# PSPS_AVNC_SRD_central-2020-09-28.net
KiCad netlist of a schematic drawn in EAGLE
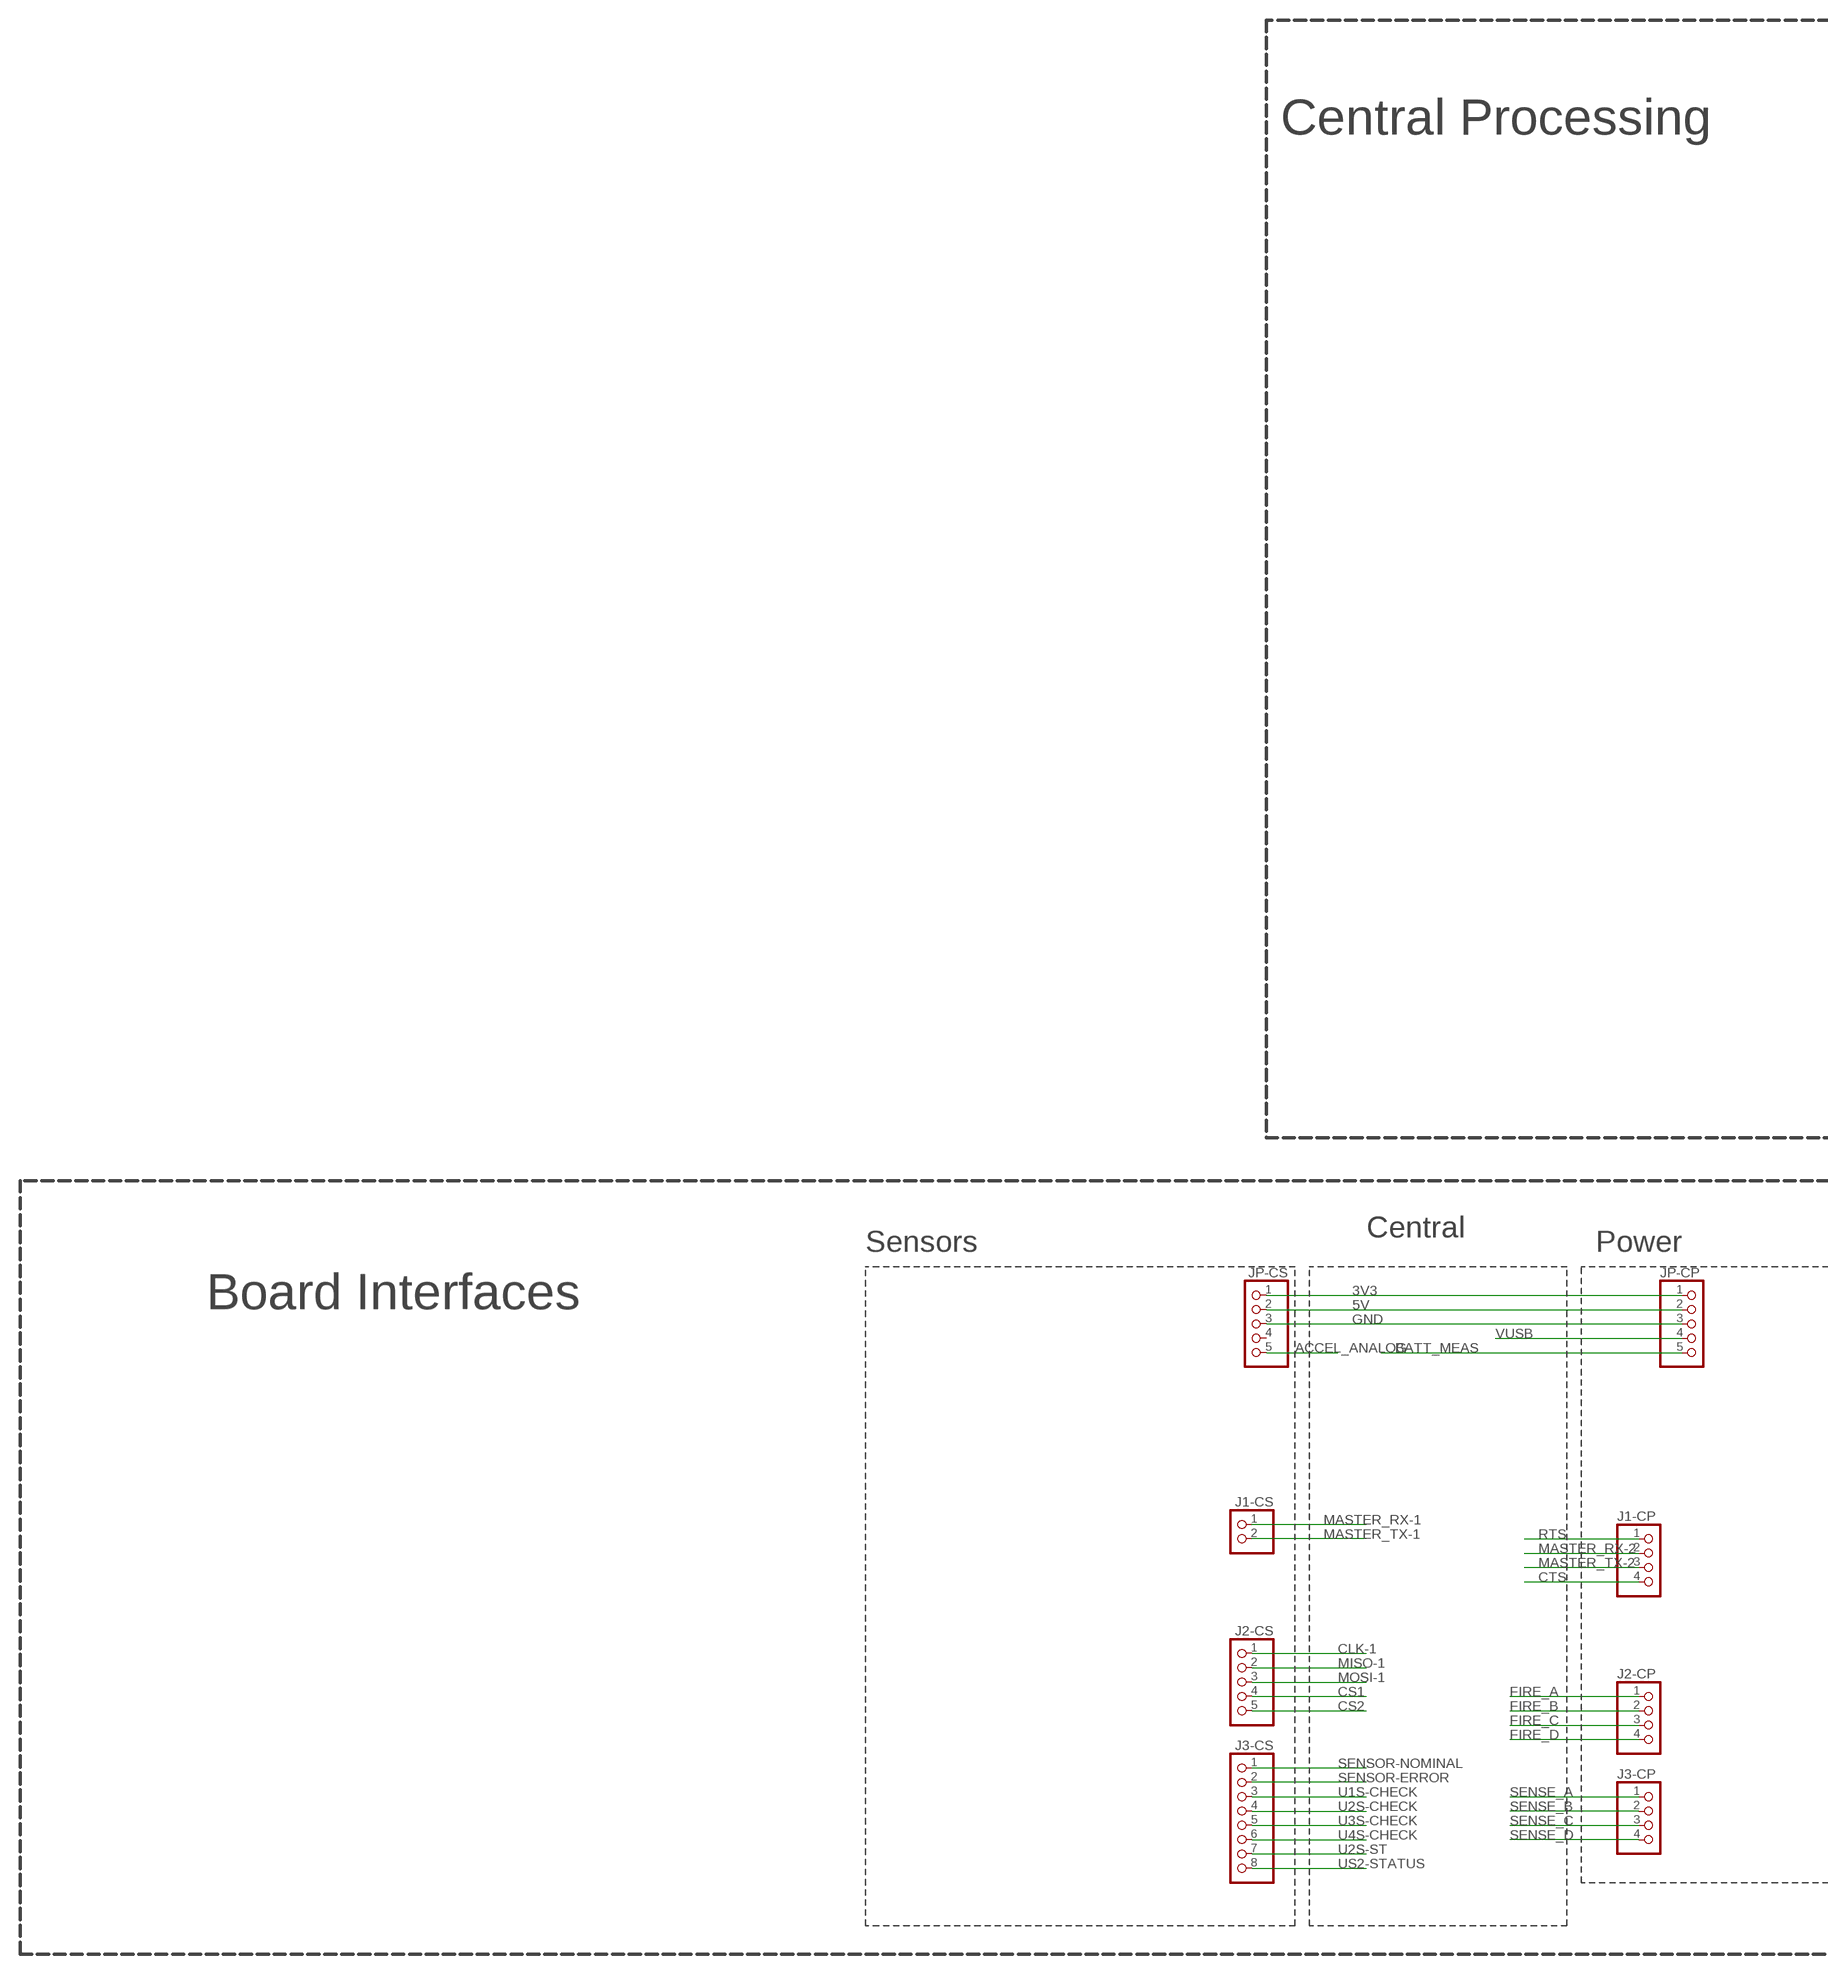
[diagram p0: schematic, sheet 1, part 1 of 2]
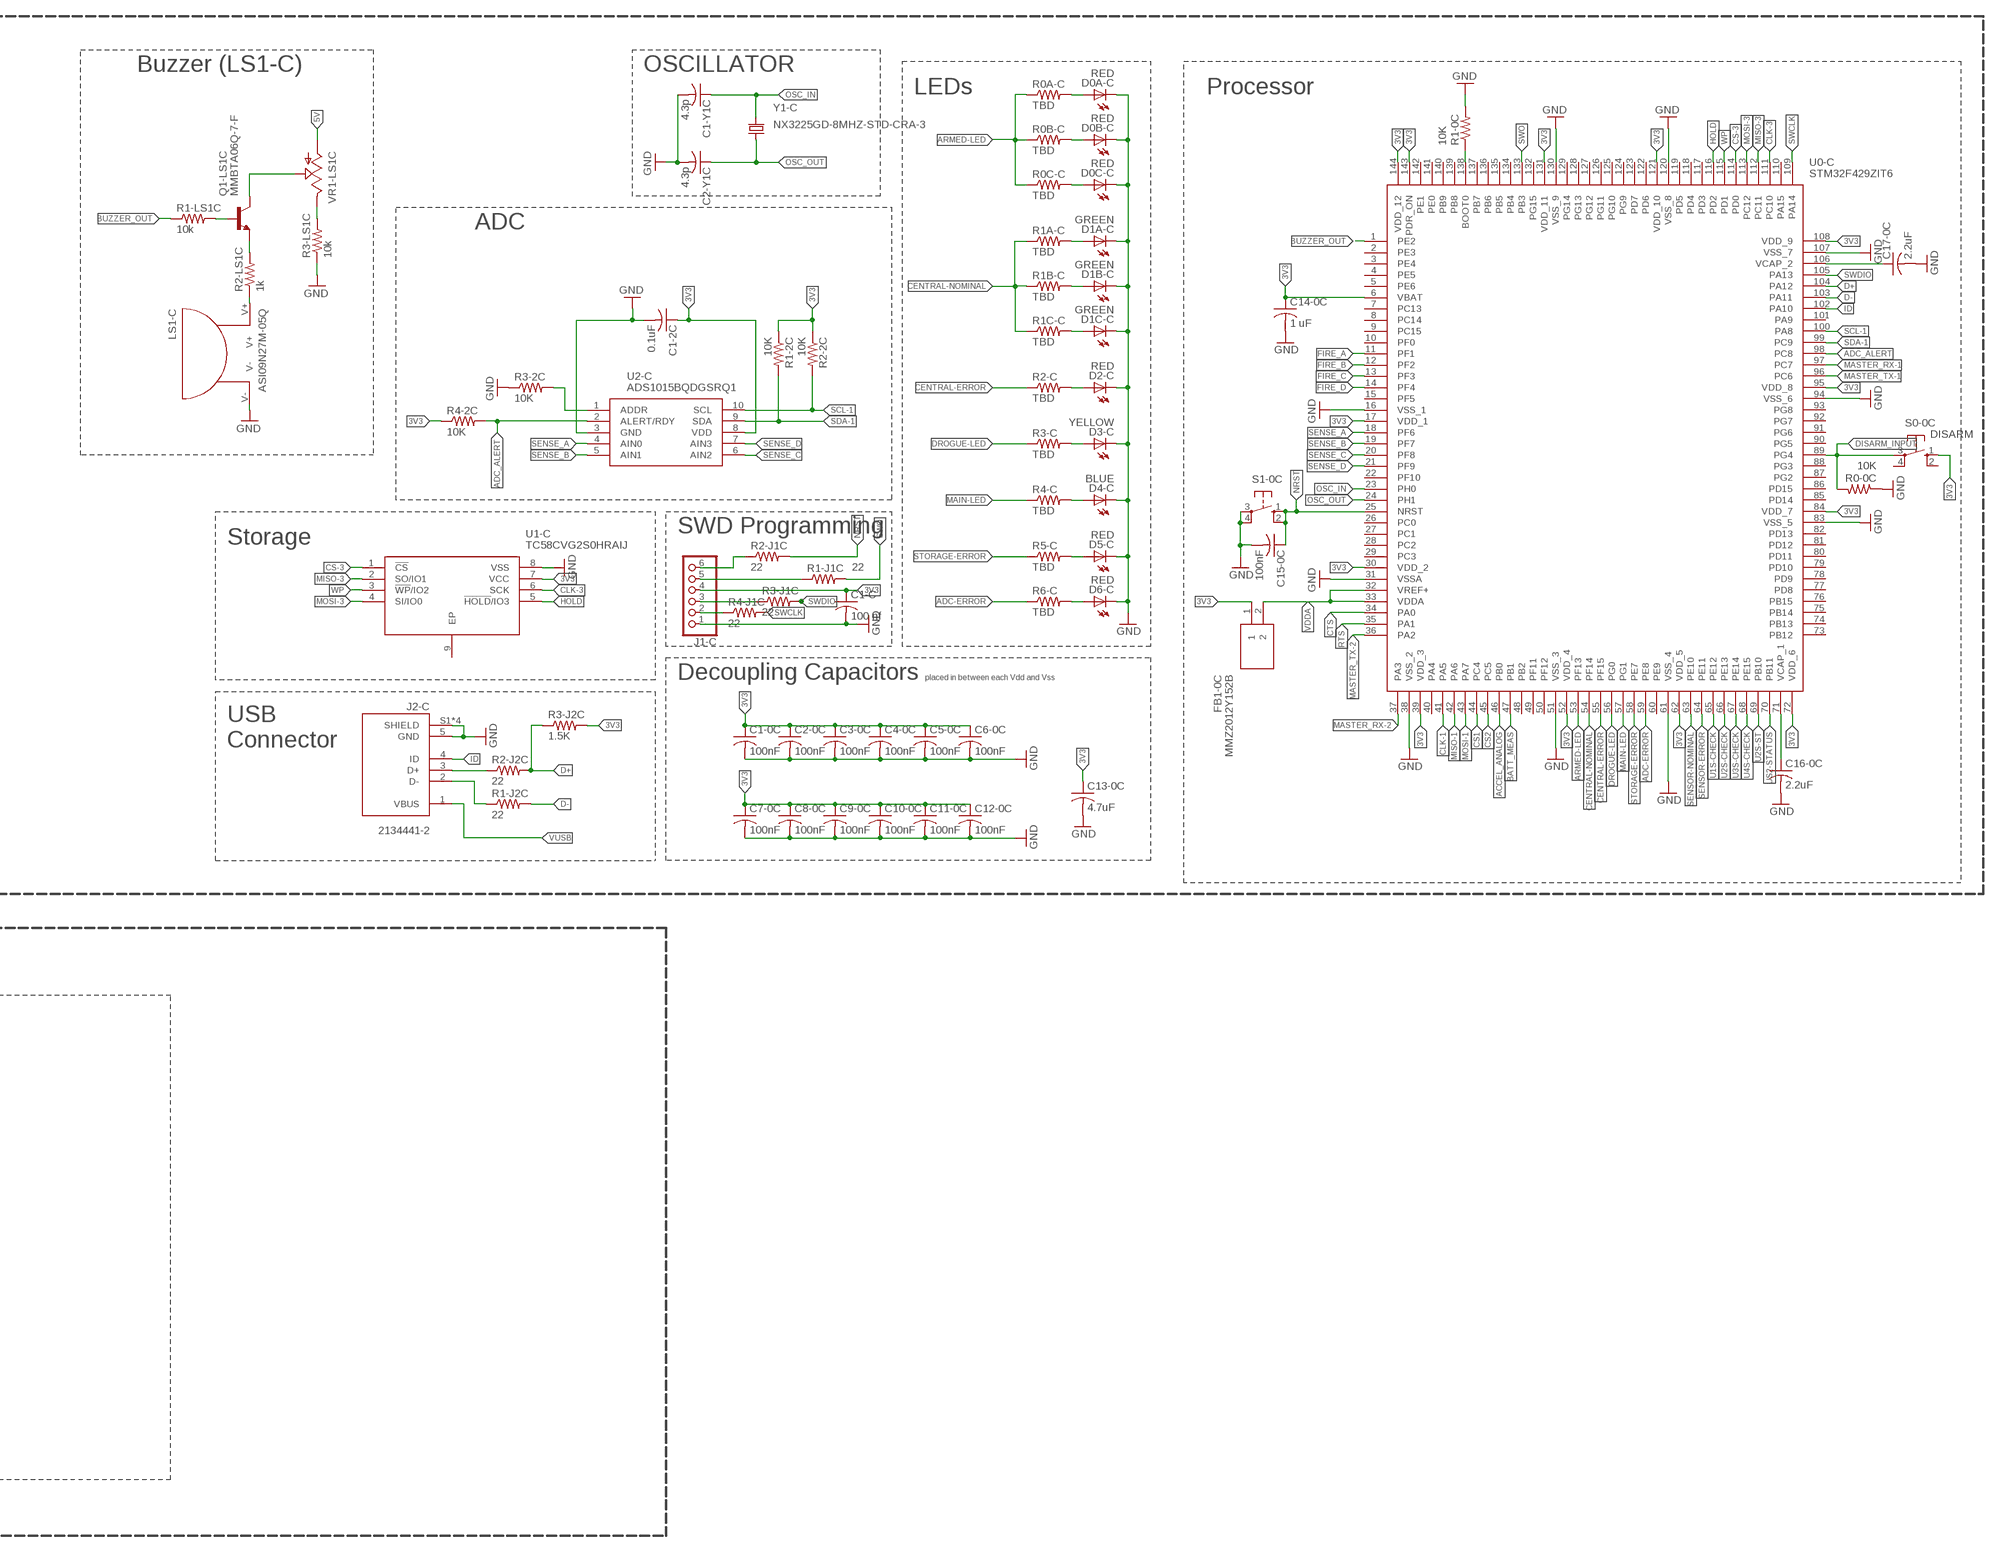
[diagram p1: schematic, sheet 1, part 2 of 2]

(export (version "E")
  (design (tool "Eeschema 10.0.6"))
  (components
    (comp (ref "C1-0C")
      (value "100nF")
      (footprint "eagle-import:C0805")
      (libsource (lib "eagle-import") (part "C-USC0805"))
    )
    (comp (ref "C1-2C")
      (value "0.1uF")
      (footprint "eagle-import:C0805")
      (libsource (lib "eagle-import") (part "C-USC0805"))
    )
    (comp (ref "C1-C")
      (value "100 nf")
      (footprint "eagle-import:C0805")
      (libsource (lib "eagle-import") (part "C-USC0805"))
    )
    (comp (ref "C1-Y1C")
      (value "4.3p")
      (footprint "eagle-import:C0805")
      (libsource (lib "eagle-import") (part "C-USC0805"))
    )
    (comp (ref "C2-0C")
      (value "100nF")
      (footprint "eagle-import:C0805")
      (libsource (lib "eagle-import") (part "C-USC0805"))
    )
    (comp (ref "C2-Y1C")
      (value "4.3p")
      (footprint "eagle-import:C0805")
      (libsource (lib "eagle-import") (part "C-USC0805"))
    )
    (comp (ref "C3-0C")
      (value "100nF")
      (footprint "eagle-import:C0805")
      (libsource (lib "eagle-import") (part "C-USC0805"))
    )
    (comp (ref "C4-0C")
      (value "100nF")
      (footprint "eagle-import:C0805")
      (libsource (lib "eagle-import") (part "C-USC0805"))
    )
    (comp (ref "C5-0C")
      (value "100nF")
      (footprint "eagle-import:C0805")
      (libsource (lib "eagle-import") (part "C-USC0805"))
    )
    (comp (ref "C6-0C")
      (value "100nF")
      (footprint "eagle-import:C0805")
      (libsource (lib "eagle-import") (part "C-USC0805"))
    )
    (comp (ref "C7-0C")
      (value "100nF")
      (footprint "eagle-import:C0805")
      (libsource (lib "eagle-import") (part "C-USC0805"))
    )
    (comp (ref "C8-0C")
      (value "100nF")
      (footprint "eagle-import:C0805")
      (libsource (lib "eagle-import") (part "C-USC0805"))
    )
    (comp (ref "C9-0C")
      (value "100nF")
      (footprint "eagle-import:C0805")
      (libsource (lib "eagle-import") (part "C-USC0805"))
    )
    (comp (ref "C10-0C")
      (value "100nF")
      (footprint "eagle-import:C0805")
      (libsource (lib "eagle-import") (part "C-USC0805"))
    )
    (comp (ref "C11-0C")
      (value "100nF")
      (footprint "eagle-import:C0805")
      (libsource (lib "eagle-import") (part "C-USC0805"))
    )
    (comp (ref "C12-0C")
      (value "100nF")
      (footprint "eagle-import:C0805")
      (libsource (lib "eagle-import") (part "C-USC0805"))
    )
    (comp (ref "C13-0C")
      (value "4.7uF")
      (footprint "eagle-import:C0805")
      (libsource (lib "eagle-import") (part "C-USC0805"))
    )
    (comp (ref "C14-0C")
      (value "1 uF")
      (footprint "eagle-import:C0805")
      (libsource (lib "eagle-import") (part "C-USC0805"))
    )
    (comp (ref "C15-0C")
      (value "100nF")
      (footprint "eagle-import:C0805")
      (libsource (lib "eagle-import") (part "C-USC0805"))
    )
    (comp (ref "C16-0C")
      (value "2.2uF")
      (footprint "eagle-import:C0805")
      (libsource (lib "eagle-import") (part "C-USC0805"))
    )
    (comp (ref "C17-0C")
      (value "2.2uF")
      (footprint "eagle-import:C0805")
      (libsource (lib "eagle-import") (part "C-USC0805"))
    )
    (comp (ref "D0A-C")
      (value "RED")
      (footprint "eagle-import:CHIPLED_0805")
      (libsource (lib "eagle-import") (part "LEDCHIPLED_0805"))
    )
    (comp (ref "D0B-C")
      (value "RED")
      (footprint "eagle-import:CHIPLED_0805")
      (libsource (lib "eagle-import") (part "LEDCHIPLED_0805"))
    )
    (comp (ref "D0C-C")
      (value "RED")
      (footprint "eagle-import:CHIPLED_0805")
      (libsource (lib "eagle-import") (part "LEDCHIPLED_0805"))
    )
    (comp (ref "D1A-C")
      (value "GREEN")
      (footprint "eagle-import:CHIPLED_0805")
      (libsource (lib "eagle-import") (part "LEDCHIPLED_0805"))
    )
    (comp (ref "D1B-C")
      (value "GREEN")
      (footprint "eagle-import:CHIPLED_0805")
      (libsource (lib "eagle-import") (part "LEDCHIPLED_0805"))
    )
    (comp (ref "D1C-C")
      (value "GREEN")
      (footprint "eagle-import:CHIPLED_0805")
      (libsource (lib "eagle-import") (part "LEDCHIPLED_0805"))
    )
    (comp (ref "D2-C")
      (value "RED")
      (footprint "eagle-import:CHIPLED_0805")
      (libsource (lib "eagle-import") (part "LEDCHIPLED_0805"))
    )
    (comp (ref "D3-C")
      (value "YELLOW")
      (footprint "eagle-import:CHIPLED_0805")
      (libsource (lib "eagle-import") (part "LEDCHIPLED_0805"))
    )
    (comp (ref "D4-C")
      (value "BLUE")
      (footprint "eagle-import:CHIPLED_0805")
      (libsource (lib "eagle-import") (part "LEDCHIPLED_0805"))
    )
    (comp (ref "D5-C")
      (value "RED")
      (footprint "eagle-import:CHIPLED_0805")
      (libsource (lib "eagle-import") (part "LEDCHIPLED_0805"))
    )
    (comp (ref "D6-C")
      (value "RED")
      (footprint "eagle-import:CHIPLED_0805")
      (libsource (lib "eagle-import") (part "LEDCHIPLED_0805"))
    )
    (comp (ref "FB1-0C")
      (value "MMZ2012Y152B")
      (footprint "eagle-import:BEADC2012X105N")
      (fields (field (name "MOUSER_PART_NUMBER") "810-MMZ2012Y152B"))
      (libsource (lib "eagle-import") (part "MMZ2012Y152B"))
    )
    (comp (ref "J1-C")
      (value "PINHD-1X6")
      (footprint "eagle-import:1X06")
      (libsource (lib "eagle-import") (part "PINHD-1X6"))
    )
    (comp (ref "J1-CP")
      (value "PINHD-1X4")
      (footprint "eagle-import:1X04")
      (libsource (lib "eagle-import") (part "PINHD-1X4"))
    )
    (comp (ref "J1-CS")
      (value "PINHD-1X2")
      (footprint "eagle-import:1X02")
      (libsource (lib "eagle-import") (part "PINHD-1X2"))
    )
    (comp (ref "J2-C")
      (value "2134441-2")
      (footprint "eagle-import:TE_2134441-2")
      (fields (field (name "DIGI-KEY_PART_NUMBER") "A118104CT-ND") (field (name "MF") "TE Connectivity"))
      (libsource (lib "eagle-import") (part "2134441-2"))
    )
    (comp (ref "J2-CP")
      (value "PINHD-1X4")
      (footprint "eagle-import:1X04")
      (libsource (lib "eagle-import") (part "PINHD-1X4"))
    )
    (comp (ref "J2-CS")
      (value "PINHD-1X5")
      (footprint "eagle-import:1X05")
      (libsource (lib "eagle-import") (part "PINHD-1X5"))
    )
    (comp (ref "J3-CP")
      (value "PINHD-1X4")
      (footprint "eagle-import:1X04")
      (libsource (lib "eagle-import") (part "PINHD-1X4"))
    )
    (comp (ref "J3-CS")
      (value "PINHD-1X8")
      (footprint "eagle-import:1X08")
      (libsource (lib "eagle-import") (part "PINHD-1X8"))
    )
    (comp (ref "JP-CP")
      (value "PINHD-1X5")
      (footprint "eagle-import:1X05")
      (libsource (lib "eagle-import") (part "PINHD-1X5"))
    )
    (comp (ref "JP-CS")
      (value "PINHD-1X5")
      (footprint "eagle-import:1X05")
      (libsource (lib "eagle-import") (part "PINHD-1X5"))
    )
    (comp (ref "LS1-C")
      (value "ASI09N27M-05Q")
      (footprint "eagle-import:ASI09N27M-05Q")
      (libsource (lib "eagle-import") (part "ASI09N27M-05Q"))
    )
    (comp (ref "Q1-LS1C")
      (value "MMBTA06Q-7-F")
      (footprint "eagle-import:SOT23")
      (libsource (lib "eagle-import") (part "NPN_TRANSISTOR"))
    )
    (comp (ref "R0-0C")
      (value "10K")
      (footprint "eagle-import:R0805")
      (libsource (lib "eagle-import") (part "R-US_R0805"))
    )
    (comp (ref "R0A-C")
      (value "TBD")
      (footprint "eagle-import:M0805")
      (libsource (lib "eagle-import") (part "R-US_M0805"))
    )
    (comp (ref "R0B-C")
      (value "TBD")
      (footprint "eagle-import:M0805")
      (libsource (lib "eagle-import") (part "R-US_M0805"))
    )
    (comp (ref "R0C-C")
      (value "TBD")
      (footprint "eagle-import:M0805")
      (libsource (lib "eagle-import") (part "R-US_M0805"))
    )
    (comp (ref "R1-0C")
      (value "10K")
      (footprint "eagle-import:R0805")
      (libsource (lib "eagle-import") (part "R-US_R0805"))
    )
    (comp (ref "R1-2C")
      (value "10K")
      (footprint "eagle-import:R0805")
      (libsource (lib "eagle-import") (part "R-US_R0805"))
    )
    (comp (ref "R1-J1C")
      (value "22")
      (footprint "eagle-import:M0805")
      (libsource (lib "eagle-import") (part "R-US_M0805"))
    )
    (comp (ref "R1-J2C")
      (value "22")
      (footprint "eagle-import:M0805")
      (libsource (lib "eagle-import") (part "R-US_M0805"))
    )
    (comp (ref "R1-LS1C")
      (value "10k")
      (footprint "eagle-import:R0805")
      (libsource (lib "eagle-import") (part "resistor_348_R-US_R0805"))
    )
    (comp (ref "R1A-C")
      (value "TBD")
      (footprint "eagle-import:M0805")
      (libsource (lib "eagle-import") (part "R-US_M0805"))
    )
    (comp (ref "R1B-C")
      (value "TBD")
      (footprint "eagle-import:M0805")
      (libsource (lib "eagle-import") (part "R-US_M0805"))
    )
    (comp (ref "R1C-C")
      (value "TBD")
      (footprint "eagle-import:M0805")
      (libsource (lib "eagle-import") (part "R-US_M0805"))
    )
    (comp (ref "R2-2C")
      (value "10K")
      (footprint "eagle-import:R0805")
      (libsource (lib "eagle-import") (part "R-US_R0805"))
    )
    (comp (ref "R2-C")
      (value "TBD")
      (footprint "eagle-import:M0805")
      (libsource (lib "eagle-import") (part "R-US_M0805"))
    )
    (comp (ref "R2-J1C")
      (value "22")
      (footprint "eagle-import:M0805")
      (libsource (lib "eagle-import") (part "R-US_M0805"))
    )
    (comp (ref "R2-J2C")
      (value "22")
      (footprint "eagle-import:M0805")
      (libsource (lib "eagle-import") (part "R-US_M0805"))
    )
    (comp (ref "R2-LS1C")
      (value "1k")
      (footprint "eagle-import:R0805")
      (libsource (lib "eagle-import") (part "resistor_348_R-US_R0805"))
    )
    (comp (ref "R3-2C")
      (value "10K")
      (footprint "eagle-import:R0805")
      (libsource (lib "eagle-import") (part "R-US_R0805"))
    )
    (comp (ref "R3-C")
      (value "TBD")
      (footprint "eagle-import:M0805")
      (libsource (lib "eagle-import") (part "R-US_M0805"))
    )
    (comp (ref "R3-J1C")
      (value "22")
      (footprint "eagle-import:M0805")
      (libsource (lib "eagle-import") (part "R-US_M0805"))
    )
    (comp (ref "R3-J2C")
      (value "1.5K")
      (footprint "eagle-import:M0805")
      (libsource (lib "eagle-import") (part "R-US_M0805"))
    )
    (comp (ref "R3-LS1C")
      (value "10k")
      (footprint "eagle-import:R0805")
      (libsource (lib "eagle-import") (part "resistor_348_R-US_R0805"))
    )
    (comp (ref "R4-2C")
      (value "10K")
      (footprint "eagle-import:R0805")
      (libsource (lib "eagle-import") (part "R-US_R0805"))
    )
    (comp (ref "R4-C")
      (value "TBD")
      (footprint "eagle-import:M0805")
      (libsource (lib "eagle-import") (part "R-US_M0805"))
    )
    (comp (ref "R4-J1C")
      (value "22")
      (footprint "eagle-import:M0805")
      (libsource (lib "eagle-import") (part "R-US_M0805"))
    )
    (comp (ref "R5-C")
      (value "TBD")
      (footprint "eagle-import:M0805")
      (libsource (lib "eagle-import") (part "R-US_M0805"))
    )
    (comp (ref "R6-C")
      (value "TBD")
      (footprint "eagle-import:M0805")
      (libsource (lib "eagle-import") (part "R-US_M0805"))
    )
    (comp (ref "S0-0C")
      (value "DISARM")
      (footprint "eagle-import:B3F-10XX")
      (fields (field (name "MPN") "B3F-1000"))
      (libsource (lib "eagle-import") (part "10-XX"))
    )
    (comp (ref "S1-0C")
      (value "10-XX")
      (footprint "eagle-import:B3F-10XX")
      (fields (field (name "MPN") "B3F-1000"))
      (libsource (lib "eagle-import") (part "10-XX"))
    )
    (comp (ref "U0-C")
      (value "STM32F429ZIT6")
      (footprint "eagle-import:QFP50P2200X2200X160-144N")
      (fields (field (name "MOUSER_PART_NUMBER") "511-STM32F429ZIT6"))
      (libsource (lib "eagle-import") (part "STM32F429ZIT6"))
    )
    (comp (ref "U1-C")
      (value "TC58CVG2S0HRAIJ")
      (footprint "eagle-import:SON127P800X600X80-9N")
      (fields (field (name "MOUSER_PART_NUMBER") "757-TC58CVG2S0HRAIJ"))
      (libsource (lib "eagle-import") (part "TC58CVG2S0HRAIJ"))
    )
    (comp (ref "U2-C")
      (value "ADS1015BQDGSRQ1")
      (footprint "eagle-import:SOP50P490X110-10N")
      (fields (field (name "MOUSER_PART_NUMBER") "595-ADS1015BQDGSRQ1"))
      (libsource (lib "eagle-import") (part "ADS1015BQDGSRQ1"))
    )
    (comp (ref "VR1-LS1C")
      (value "TRIM_US-LI10")
      (footprint "eagle-import:LI10")
      (libsource (lib "eagle-import") (part "TRIM_US-LI10"))
    )
    (comp (ref "Y1-C")
      (value "NX3225GD-8MHZ-STD-CRA-3")
      (footprint "eagle-import:NX3225GD")
      (libsource (lib "eagle-import") (part "NX3225GD"))
    )
  )
  (nets
    (net (code "1") (name "3V3") (class "Default")
      (node (ref "C1-0C") (pin "1") (pinfunction "1_1") (pintype "passive"))
      (node (ref "C1-2C") (pin "1") (pinfunction "1_1") (pintype "passive"))
      (node (ref "C1-C") (pin "1") (pinfunction "1_1") (pintype "passive"))
      (node (ref "C10-0C") (pin "1") (pinfunction "1_1") (pintype "passive"))
      (node (ref "C11-0C") (pin "1") (pinfunction "1_1") (pintype "passive"))
      (node (ref "C12-0C") (pin "1") (pinfunction "1_1") (pintype "passive"))
      (node (ref "C13-0C") (pin "1") (pinfunction "1_1") (pintype "passive"))
      (node (ref "C14-0C") (pin "1") (pinfunction "1_1") (pintype "passive"))
      (node (ref "C2-0C") (pin "1") (pinfunction "1_1") (pintype "passive"))
      (node (ref "C3-0C") (pin "1") (pinfunction "1_1") (pintype "passive"))
      (node (ref "C4-0C") (pin "1") (pinfunction "1_1") (pintype "passive"))
      (node (ref "C5-0C") (pin "1") (pinfunction "1_1") (pintype "passive"))
      (node (ref "C6-0C") (pin "1") (pinfunction "1_1") (pintype "passive"))
      (node (ref "C7-0C") (pin "1") (pinfunction "1_1") (pintype "passive"))
      (node (ref "C8-0C") (pin "1") (pinfunction "1_1") (pintype "passive"))
      (node (ref "C9-0C") (pin "1") (pinfunction "1_1") (pintype "passive"))
      (node (ref "FB1-0C") (pin "1") (pinfunction "1_1") (pintype "bidirectional"))
      (node (ref "J1-C") (pin "4") (pinfunction "4_4") (pintype "passive"))
      (node (ref "JP-CP") (pin "1") (pinfunction "1_1") (pintype "passive"))
      (node (ref "JP-CS") (pin "1") (pinfunction "1_1") (pintype "passive"))
      (node (ref "R1-2C") (pin "1") (pinfunction "1_1") (pintype "passive"))
      (node (ref "R2-2C") (pin "1") (pinfunction "1_1") (pintype "passive"))
      (node (ref "R3-J2C") (pin "2") (pinfunction "2_2") (pintype "passive"))
      (node (ref "R4-2C") (pin "1") (pinfunction "1_1") (pintype "passive"))
      (node (ref "S0-0C") (pin "1") (pinfunction "S_1") (pintype "passive"))
      (node (ref "U0-C") (pin "108") (pinfunction "VDD_9_108") (pintype "power_in"))
      (node (ref "U0-C") (pin "121") (pinfunction "VDD_10_121") (pintype "power_in"))
      (node (ref "U0-C") (pin "131") (pinfunction "VDD_11_131") (pintype "power_in"))
      (node (ref "U0-C") (pin "143") (pinfunction "PDR_ON_143") (pintype "bidirectional"))
      (node (ref "U0-C") (pin "144") (pinfunction "VDD_12_144") (pintype "power_in"))
      (node (ref "U0-C") (pin "17") (pinfunction "VDD_1_17") (pintype "power_in"))
      (node (ref "U0-C") (pin "30") (pinfunction "VDD_2_30") (pintype "power_in"))
      (node (ref "U0-C") (pin "39") (pinfunction "VDD_3_39") (pintype "power_in"))
      (node (ref "U0-C") (pin "52") (pinfunction "VDD_4_52") (pintype "power_in"))
      (node (ref "U0-C") (pin "6") (pinfunction "VBAT_6") (pintype "bidirectional"))
      (node (ref "U0-C") (pin "62") (pinfunction "VDD_5_62") (pintype "power_in"))
      (node (ref "U0-C") (pin "72") (pinfunction "VDD_6_72") (pintype "power_in"))
      (node (ref "U0-C") (pin "84") (pinfunction "VDD_7_84") (pintype "power_in"))
      (node (ref "U0-C") (pin "95") (pinfunction "VDD_8_95") (pintype "power_in"))
      (node (ref "U1-C") (pin "7") (pinfunction "VCC_7") (pintype "bidirectional"))
      (node (ref "U2-C") (pin "8") (pinfunction "VDD_8") (pintype "bidirectional"))
    )
    (net (code "2") (name "5V") (class "Default")
      (node (ref "JP-CP") (pin "2") (pinfunction "2_2") (pintype "passive"))
      (node (ref "JP-CS") (pin "2") (pinfunction "2_2") (pintype "passive"))
      (node (ref "VR1-LS1C") (pin "A") (pinfunction "A_A") (pintype "passive"))
    )
    (net (code "3") (name "ACCEL_ANALOG") (class "Default")
      (node (ref "JP-CS") (pin "5") (pinfunction "5_5") (pintype "passive"))
      (node (ref "U0-C") (pin "46") (pinfunction "PB0_46") (pintype "bidirectional"))
    )
    (net (code "4") (name "ADC-ERROR") (class "Default")
      (node (ref "R6-C") (pin "1") (pinfunction "1_1") (pintype "passive"))
      (node (ref "U0-C") (pin "59") (pinfunction "PE8_59") (pintype "bidirectional"))
    )
    (net (code "5") (name "ADC_ALERT") (class "Default")
      (node (ref "R4-2C") (pin "2") (pinfunction "2_2") (pintype "passive"))
      (node (ref "U0-C") (pin "98") (pinfunction "PC8_98") (pintype "bidirectional"))
      (node (ref "U2-C") (pin "2") (pinfunction "ALERT/RDY_2") (pintype "bidirectional"))
    )
    (net (code "6") (name "ARMED-LED") (class "Default")
      (node (ref "R0A-C") (pin "1") (pinfunction "1_1") (pintype "passive"))
      (node (ref "R0B-C") (pin "1") (pinfunction "1_1") (pintype "passive"))
      (node (ref "R0C-C") (pin "1") (pinfunction "1_1") (pintype "passive"))
      (node (ref "U0-C") (pin "53") (pinfunction "PF13_53") (pintype "bidirectional"))
    )
    (net (code "7") (name "BATT_MEAS") (class "Default")
      (node (ref "JP-CP") (pin "5") (pinfunction "5_5") (pintype "passive"))
      (node (ref "U0-C") (pin "47") (pinfunction "PB1_47") (pintype "bidirectional"))
    )
    (net (code "8") (name "BUZZER_OUT") (class "Default")
      (node (ref "R1-LS1C") (pin "1") (pinfunction "1_1") (pintype "passive"))
      (node (ref "U0-C") (pin "1") (pinfunction "PE2_1") (pintype "bidirectional"))
    )
    (net (code "9") (name "CENTRAL-ERROR") (class "Default")
      (node (ref "R2-C") (pin "1") (pinfunction "1_1") (pintype "passive"))
      (node (ref "U0-C") (pin "55") (pinfunction "PF15_55") (pintype "bidirectional"))
    )
    (net (code "10") (name "CENTRAL-NOMINAL") (class "Default")
      (node (ref "R1A-C") (pin "1") (pinfunction "1_1") (pintype "passive"))
      (node (ref "R1B-C") (pin "1") (pinfunction "1_1") (pintype "passive"))
      (node (ref "R1C-C") (pin "1") (pinfunction "1_1") (pintype "passive"))
      (node (ref "U0-C") (pin "54") (pinfunction "PF14_54") (pintype "bidirectional"))
    )
    (net (code "11") (name "CLK-1") (class "Default")
      (node (ref "J2-CS") (pin "1") (pinfunction "1_1") (pintype "passive"))
      (node (ref "U0-C") (pin "41") (pinfunction "PA5_41") (pintype "bidirectional"))
    )
    (net (code "12") (name "CLK-3") (class "Default")
      (node (ref "U0-C") (pin "111") (pinfunction "PC10_111") (pintype "bidirectional"))
      (node (ref "U1-C") (pin "6") (pinfunction "SCK_6") (pintype "bidirectional"))
    )
    (net (code "13") (name "CS-3") (class "Default")
      (node (ref "U0-C") (pin "114") (pinfunction "PD0_114") (pintype "bidirectional"))
      (node (ref "U1-C") (pin "1") (pinfunction "~{CS}_1") (pintype "bidirectional"))
    )
    (net (code "14") (name "CS1") (class "Default")
      (node (ref "J2-CS") (pin "4") (pinfunction "4_4") (pintype "passive"))
      (node (ref "U0-C") (pin "44") (pinfunction "PC4_44") (pintype "bidirectional"))
    )
    (net (code "15") (name "CS2") (class "Default")
      (node (ref "J2-CS") (pin "5") (pinfunction "5_5") (pintype "passive"))
      (node (ref "U0-C") (pin "45") (pinfunction "PC5_45") (pintype "bidirectional"))
    )
    (net (code "16") (name "CTS") (class "Default")
      (node (ref "J1-CP") (pin "4") (pinfunction "4_4") (pintype "passive"))
      (node (ref "U0-C") (pin "34") (pinfunction "PA0_34") (pintype "bidirectional"))
    )
    (net (code "17") (name "D+") (class "Default")
      (node (ref "R2-J2C") (pin "2") (pinfunction "2_2") (pintype "passive"))
      (node (ref "R3-J2C") (pin "1") (pinfunction "1_1") (pintype "passive"))
      (node (ref "U0-C") (pin "104") (pinfunction "PA12_104") (pintype "bidirectional"))
    )
    (net (code "18") (name "D-") (class "Default")
      (node (ref "R1-J2C") (pin "2") (pinfunction "2_2") (pintype "passive"))
      (node (ref "U0-C") (pin "103") (pinfunction "PA11_103") (pintype "bidirectional"))
    )
    (net (code "19") (name "DISARM_INPUT") (class "Default")
      (node (ref "R0-0C") (pin "2") (pinfunction "2_2") (pintype "passive"))
      (node (ref "S0-0C") (pin "3") (pinfunction "P_3") (pintype "passive"))
      (node (ref "U0-C") (pin "89") (pinfunction "PG4_89") (pintype "bidirectional"))
    )
    (net (code "20") (name "DROGUE-LED") (class "Default")
      (node (ref "R3-C") (pin "1") (pinfunction "1_1") (pintype "passive"))
      (node (ref "U0-C") (pin "56") (pinfunction "PG0_56") (pintype "bidirectional"))
    )
    (net (code "21") (name "FIRE_A") (class "Default")
      (node (ref "J2-CP") (pin "1") (pinfunction "1_1") (pintype "passive"))
      (node (ref "U0-C") (pin "11") (pinfunction "PF1_11") (pintype "bidirectional"))
    )
    (net (code "22") (name "FIRE_B") (class "Default")
      (node (ref "J2-CP") (pin "2") (pinfunction "2_2") (pintype "passive"))
      (node (ref "U0-C") (pin "12") (pinfunction "PF2_12") (pintype "bidirectional"))
    )
    (net (code "23") (name "FIRE_C") (class "Default")
      (node (ref "J2-CP") (pin "3") (pinfunction "3_3") (pintype "passive"))
      (node (ref "U0-C") (pin "13") (pinfunction "PF3_13") (pintype "bidirectional"))
    )
    (net (code "24") (name "FIRE_D") (class "Default")
      (node (ref "J2-CP") (pin "4") (pinfunction "4_4") (pintype "passive"))
      (node (ref "U0-C") (pin "14") (pinfunction "PF4_14") (pintype "bidirectional"))
    )
    (net (code "25") (name "GND") (class "Default")
      (node (ref "C1-0C") (pin "2") (pinfunction "2_2") (pintype "passive"))
      (node (ref "C1-2C") (pin "2") (pinfunction "2_2") (pintype "passive"))
      (node (ref "C1-C") (pin "2") (pinfunction "2_2") (pintype "passive"))
      (node (ref "C1-Y1C") (pin "2") (pinfunction "2_2") (pintype "passive"))
      (node (ref "C10-0C") (pin "2") (pinfunction "2_2") (pintype "passive"))
      (node (ref "C11-0C") (pin "2") (pinfunction "2_2") (pintype "passive"))
      (node (ref "C12-0C") (pin "2") (pinfunction "2_2") (pintype "passive"))
      (node (ref "C13-0C") (pin "2") (pinfunction "2_2") (pintype "passive"))
      (node (ref "C14-0C") (pin "2") (pinfunction "2_2") (pintype "passive"))
      (node (ref "C15-0C") (pin "2") (pinfunction "2_2") (pintype "passive"))
      (node (ref "C16-0C") (pin "2") (pinfunction "2_2") (pintype "passive"))
      (node (ref "C17-0C") (pin "2") (pinfunction "2_2") (pintype "passive"))
      (node (ref "C2-0C") (pin "2") (pinfunction "2_2") (pintype "passive"))
      (node (ref "C2-Y1C") (pin "2") (pinfunction "2_2") (pintype "passive"))
      (node (ref "C3-0C") (pin "2") (pinfunction "2_2") (pintype "passive"))
      (node (ref "C4-0C") (pin "2") (pinfunction "2_2") (pintype "passive"))
      (node (ref "C5-0C") (pin "2") (pinfunction "2_2") (pintype "passive"))
      (node (ref "C6-0C") (pin "2") (pinfunction "2_2") (pintype "passive"))
      (node (ref "C7-0C") (pin "2") (pinfunction "2_2") (pintype "passive"))
      (node (ref "C8-0C") (pin "2") (pinfunction "2_2") (pintype "passive"))
      (node (ref "C9-0C") (pin "2") (pinfunction "2_2") (pintype "passive"))
      (node (ref "D0A-C") (pin "C") (pinfunction "C_C") (pintype "passive"))
      (node (ref "D0B-C") (pin "C") (pinfunction "C_C") (pintype "passive"))
      (node (ref "D0C-C") (pin "C") (pinfunction "C_C") (pintype "passive"))
      (node (ref "D1A-C") (pin "C") (pinfunction "C_C") (pintype "passive"))
      (node (ref "D1B-C") (pin "C") (pinfunction "C_C") (pintype "passive"))
      (node (ref "D1C-C") (pin "C") (pinfunction "C_C") (pintype "passive"))
      (node (ref "D2-C") (pin "C") (pinfunction "C_C") (pintype "passive"))
      (node (ref "D3-C") (pin "C") (pinfunction "C_C") (pintype "passive"))
      (node (ref "D4-C") (pin "C") (pinfunction "C_C") (pintype "passive"))
      (node (ref "D5-C") (pin "C") (pinfunction "C_C") (pintype "passive"))
      (node (ref "D6-C") (pin "C") (pinfunction "C_C") (pintype "passive"))
      (node (ref "J1-C") (pin "1") (pinfunction "1_1") (pintype "passive"))
      (node (ref "J2-C") (pin "5") (pinfunction "GND_5") (pintype "power_in"))
      (node (ref "J2-C") (pin "S1") (pinfunction "SHIELD_S1") (pintype "power_in"))
      (node (ref "J2-C") (pin "S2") (pinfunction "SHIELD_S2") (pintype "power_in"))
      (node (ref "J2-C") (pin "S3") (pinfunction "SHIELD_S3") (pintype "power_in"))
      (node (ref "J2-C") (pin "S4") (pinfunction "SHIELD_S4") (pintype "power_in"))
      (node (ref "JP-CP") (pin "3") (pinfunction "3_3") (pintype "passive"))
      (node (ref "JP-CS") (pin "3") (pinfunction "3_3") (pintype "passive"))
      (node (ref "LS1-C") (pin "V-") (pinfunction "V-_V-") (pintype "bidirectional"))
      (node (ref "R0-0C") (pin "1") (pinfunction "1_1") (pintype "passive"))
      (node (ref "R1-0C") (pin "2") (pinfunction "2_2") (pintype "passive"))
      (node (ref "R3-2C") (pin "1") (pinfunction "1_1") (pintype "passive"))
      (node (ref "R3-LS1C") (pin "1") (pinfunction "1_1") (pintype "passive"))
      (node (ref "S1-0C") (pin "3") (pinfunction "P_3") (pintype "passive"))
      (node (ref "S1-0C") (pin "4") (pinfunction "P1_4") (pintype "passive"))
      (node (ref "U0-C") (pin "107") (pinfunction "VSS_7_107") (pintype "power_in"))
      (node (ref "U0-C") (pin "120") (pinfunction "VSS_8_120") (pintype "power_in"))
      (node (ref "U0-C") (pin "130") (pinfunction "VSS_9_130") (pintype "power_in"))
      (node (ref "U0-C") (pin "16") (pinfunction "VSS_1_16") (pintype "power_in"))
      (node (ref "U0-C") (pin "31") (pinfunction "VSSA_31") (pintype "power_in"))
      (node (ref "U0-C") (pin "38") (pinfunction "VSS_2_38") (pintype "power_in"))
      (node (ref "U0-C") (pin "51") (pinfunction "VSS_3_51") (pintype "power_in"))
      (node (ref "U0-C") (pin "61") (pinfunction "VSS_4_61") (pintype "power_in"))
      (node (ref "U0-C") (pin "83") (pinfunction "VSS_5_83") (pintype "power_in"))
      (node (ref "U0-C") (pin "94") (pinfunction "VSS_6_94") (pintype "power_in"))
      (node (ref "U1-C") (pin "8") (pinfunction "VSS_8") (pintype "bidirectional"))
      (node (ref "U2-C") (pin "3") (pinfunction "GND_3") (pintype "bidirectional"))
    )
    (net (code "26") (name "HOLD") (class "Default")
      (node (ref "U0-C") (pin "116") (pinfunction "PD2_116") (pintype "bidirectional"))
      (node (ref "U1-C") (pin "5") (pinfunction "~{HOLD}/IO3_5") (pintype "bidirectional"))
    )
    (net (code "27") (name "ID") (class "Default")
      (node (ref "J2-C") (pin "4") (pinfunction "ID_4") (pintype "bidirectional"))
      (node (ref "U0-C") (pin "102") (pinfunction "PA10_102") (pintype "bidirectional"))
    )
    (net (code "28") (name "MAIN-LED") (class "Default")
      (node (ref "R4-C") (pin "1") (pinfunction "1_1") (pintype "passive"))
      (node (ref "U0-C") (pin "57") (pinfunction "PG1_57") (pintype "bidirectional"))
    )
    (net (code "29") (name "MASTER_RX-1") (class "Default")
      (node (ref "J1-CS") (pin "1") (pinfunction "1_1") (pintype "passive"))
      (node (ref "U0-C") (pin "97") (pinfunction "PC7_97") (pintype "bidirectional"))
    )
    (net (code "30") (name "MASTER_RX-2") (class "Default")
      (node (ref "J1-CP") (pin "2") (pinfunction "2_2") (pintype "passive"))
      (node (ref "U0-C") (pin "37") (pinfunction "PA3_37") (pintype "bidirectional"))
    )
    (net (code "31") (name "MASTER_TX-1") (class "Default")
      (node (ref "J1-CS") (pin "2") (pinfunction "2_2") (pintype "passive"))
      (node (ref "U0-C") (pin "96") (pinfunction "PC6_96") (pintype "bidirectional"))
    )
    (net (code "32") (name "MASTER_TX-2") (class "Default")
      (node (ref "J1-CP") (pin "3") (pinfunction "3_3") (pintype "passive"))
      (node (ref "U0-C") (pin "36") (pinfunction "PA2_36") (pintype "bidirectional"))
    )
    (net (code "33") (name "MISO-1") (class "Default")
      (node (ref "J2-CS") (pin "2") (pinfunction "2_2") (pintype "passive"))
      (node (ref "U0-C") (pin "42") (pinfunction "PA6_42") (pintype "bidirectional"))
    )
    (net (code "34") (name "MISO-3") (class "Default")
      (node (ref "U0-C") (pin "112") (pinfunction "PC11_112") (pintype "bidirectional"))
      (node (ref "U1-C") (pin "2") (pinfunction "SO/IO1_2") (pintype "bidirectional"))
    )
    (net (code "35") (name "MOSI-1") (class "Default")
      (node (ref "J2-CS") (pin "3") (pinfunction "3_3") (pintype "passive"))
      (node (ref "U0-C") (pin "43") (pinfunction "PA7_43") (pintype "bidirectional"))
    )
    (net (code "36") (name "MOSI-3") (class "Default")
      (node (ref "U0-C") (pin "113") (pinfunction "PC12_113") (pintype "bidirectional"))
      (node (ref "U1-C") (pin "4") (pinfunction "SI/IO0_4") (pintype "bidirectional"))
    )
    (net (code "37") (name "NRST") (class "Default")
      (node (ref "C15-0C") (pin "1") (pinfunction "1_1") (pintype "passive"))
      (node (ref "R2-J1C") (pin "2") (pinfunction "2_2") (pintype "passive"))
      (node (ref "S1-0C") (pin "1") (pinfunction "S_1") (pintype "passive"))
      (node (ref "S1-0C") (pin "2") (pinfunction "S1_2") (pintype "passive"))
      (node (ref "U0-C") (pin "25") (pinfunction "NRST_25") (pintype "input"))
    )
    (net (code "38") (name "Net-(D0A-C-PadA)") (class "Default")
      (node (ref "D0A-C") (pin "A") (pinfunction "A_A") (pintype "passive"))
      (node (ref "R0A-C") (pin "2") (pinfunction "2_2") (pintype "passive"))
    )
    (net (code "39") (name "Net-(D0B-C-PadA)") (class "Default")
      (node (ref "D0B-C") (pin "A") (pinfunction "A_A") (pintype "passive"))
      (node (ref "R0B-C") (pin "2") (pinfunction "2_2") (pintype "passive"))
    )
    (net (code "40") (name "Net-(D0C-C-PadA)") (class "Default")
      (node (ref "D0C-C") (pin "A") (pinfunction "A_A") (pintype "passive"))
      (node (ref "R0C-C") (pin "2") (pinfunction "2_2") (pintype "passive"))
    )
    (net (code "41") (name "Net-(D1A-C-PadA)") (class "Default")
      (node (ref "D1A-C") (pin "A") (pinfunction "A_A") (pintype "passive"))
      (node (ref "R1A-C") (pin "2") (pinfunction "2_2") (pintype "passive"))
    )
    (net (code "42") (name "Net-(D1B-C-PadA)") (class "Default")
      (node (ref "D1B-C") (pin "A") (pinfunction "A_A") (pintype "passive"))
      (node (ref "R1B-C") (pin "2") (pinfunction "2_2") (pintype "passive"))
    )
    (net (code "43") (name "Net-(D1C-C-PadA)") (class "Default")
      (node (ref "D1C-C") (pin "A") (pinfunction "A_A") (pintype "passive"))
      (node (ref "R1C-C") (pin "2") (pinfunction "2_2") (pintype "passive"))
    )
    (net (code "44") (name "Net-(D2-C-PadA)") (class "Default")
      (node (ref "D2-C") (pin "A") (pinfunction "A_A") (pintype "passive"))
      (node (ref "R2-C") (pin "2") (pinfunction "2_2") (pintype "passive"))
    )
    (net (code "45") (name "Net-(D3-C-PadA)") (class "Default")
      (node (ref "D3-C") (pin "A") (pinfunction "A_A") (pintype "passive"))
      (node (ref "R3-C") (pin "2") (pinfunction "2_2") (pintype "passive"))
    )
    (net (code "46") (name "Net-(D4-C-PadA)") (class "Default")
      (node (ref "D4-C") (pin "A") (pinfunction "A_A") (pintype "passive"))
      (node (ref "R4-C") (pin "2") (pinfunction "2_2") (pintype "passive"))
    )
    (net (code "47") (name "Net-(D5-C-PadA)") (class "Default")
      (node (ref "D5-C") (pin "A") (pinfunction "A_A") (pintype "passive"))
      (node (ref "R5-C") (pin "2") (pinfunction "2_2") (pintype "passive"))
    )
    (net (code "48") (name "Net-(D6-C-PadA)") (class "Default")
      (node (ref "D6-C") (pin "A") (pinfunction "A_A") (pintype "passive"))
      (node (ref "R6-C") (pin "2") (pinfunction "2_2") (pintype "passive"))
    )
    (net (code "49") (name "Net-(J1-C-Pad2)") (class "Default")
      (node (ref "J1-C") (pin "2") (pinfunction "2_2") (pintype "passive"))
      (node (ref "R4-J1C") (pin "1") (pinfunction "1_1") (pintype "passive"))
    )
    (net (code "50") (name "Net-(J1-C-Pad3)") (class "Default")
      (node (ref "J1-C") (pin "3") (pinfunction "3_3") (pintype "passive"))
      (node (ref "R3-J1C") (pin "1") (pinfunction "1_1") (pintype "passive"))
    )
    (net (code "51") (name "Net-(J1-C-Pad5)") (class "Default")
      (node (ref "J1-C") (pin "5") (pinfunction "5_5") (pintype "passive"))
      (node (ref "R1-J1C") (pin "1") (pinfunction "1_1") (pintype "passive"))
    )
    (net (code "52") (name "Net-(J1-C-Pad6)") (class "Default")
      (node (ref "J1-C") (pin "6") (pinfunction "6_6") (pintype "passive"))
      (node (ref "R2-J1C") (pin "1") (pinfunction "1_1") (pintype "passive"))
    )
    (net (code "53") (name "Net-(J2-C-D+)") (class "Default")
      (node (ref "J2-C") (pin "3") (pinfunction "D+_3") (pintype "bidirectional"))
      (node (ref "R2-J2C") (pin "1") (pinfunction "1_1") (pintype "passive"))
    )
    (net (code "54") (name "Net-(J2-C-D-)") (class "Default")
      (node (ref "J2-C") (pin "2") (pinfunction "D-_2") (pintype "bidirectional"))
      (node (ref "R1-J2C") (pin "1") (pinfunction "1_1") (pintype "passive"))
    )
    (net (code "55") (name "Net-(LS1-C-PadV+)") (class "Default")
      (node (ref "LS1-C") (pin "V+") (pinfunction "V+_V+") (pintype "bidirectional"))
      (node (ref "R2-LS1C") (pin "1") (pinfunction "1_1") (pintype "passive"))
    )
    (net (code "56") (name "Net-(Q1-LS1C-B)") (class "Default")
      (node (ref "Q1-LS1C") (pin "1") (pinfunction "B_1") (pintype "passive"))
      (node (ref "R1-LS1C") (pin "2") (pinfunction "2_2") (pintype "passive"))
    )
    (net (code "57") (name "Net-(Q1-LS1C-C)") (class "Default")
      (node (ref "Q1-LS1C") (pin "2") (pinfunction "C_2") (pintype "passive"))
      (node (ref "VR1-LS1C") (pin "S") (pinfunction "S_S") (pintype "passive"))
    )
    (net (code "58") (name "Net-(Q1-LS1C-E)") (class "Default")
      (node (ref "Q1-LS1C") (pin "3") (pinfunction "E_3") (pintype "passive"))
      (node (ref "R2-LS1C") (pin "2") (pinfunction "2_2") (pintype "passive"))
    )
    (net (code "59") (name "Net-(R3-LS1C-Pad2)") (class "Default")
      (node (ref "R3-LS1C") (pin "2") (pinfunction "2_2") (pintype "passive"))
      (node (ref "VR1-LS1C") (pin "E") (pinfunction "E_E") (pintype "passive"))
    )
    (net (code "60") (name "Net-(U0-C-BOOT0)") (class "Default")
      (node (ref "R1-0C") (pin "1") (pinfunction "1_1") (pintype "passive"))
      (node (ref "U0-C") (pin "138") (pinfunction "BOOT0_138") (pintype "bidirectional"))
    )
    (net (code "61") (name "Net-(U0-C-VCAP_1)") (class "Default")
      (node (ref "C16-0C") (pin "1") (pinfunction "1_1") (pintype "passive"))
      (node (ref "U0-C") (pin "71") (pinfunction "VCAP_1_71") (pintype "bidirectional"))
    )
    (net (code "62") (name "Net-(U0-C-VCAP_2)") (class "Default")
      (node (ref "C17-0C") (pin "1") (pinfunction "1_1") (pintype "passive"))
      (node (ref "U0-C") (pin "106") (pinfunction "VCAP_2_106") (pintype "bidirectional"))
    )
    (net (code "63") (name "Net-(U2-C-ADDR)") (class "Default")
      (node (ref "R3-2C") (pin "2") (pinfunction "2_2") (pintype "passive"))
      (node (ref "U2-C") (pin "1") (pinfunction "ADDR_1") (pintype "bidirectional"))
    )
    (net (code "64") (name "OSC_IN") (class "Default")
      (node (ref "C1-Y1C") (pin "1") (pinfunction "1_1") (pintype "passive"))
      (node (ref "U0-C") (pin "23") (pinfunction "PH0_23") (pintype "bidirectional"))
      (node (ref "Y1-C") (pin "P$2") (pinfunction "2_P$2") (pintype "passive"))
    )
    (net (code "65") (name "OSC_OUT") (class "Default")
      (node (ref "C2-Y1C") (pin "1") (pinfunction "1_1") (pintype "passive"))
      (node (ref "U0-C") (pin "24") (pinfunction "PH1_24") (pintype "bidirectional"))
      (node (ref "Y1-C") (pin "P$1") (pinfunction "1_P$1") (pintype "passive"))
    )
    (net (code "66") (name "RTS") (class "Default")
      (node (ref "J1-CP") (pin "1") (pinfunction "1_1") (pintype "passive"))
      (node (ref "U0-C") (pin "35") (pinfunction "PA1_35") (pintype "bidirectional"))
    )
    (net (code "67") (name "SCL-1") (class "Default")
      (node (ref "R2-2C") (pin "2") (pinfunction "2_2") (pintype "passive"))
      (node (ref "U0-C") (pin "100") (pinfunction "PA8_100") (pintype "bidirectional"))
      (node (ref "U2-C") (pin "10") (pinfunction "SCL_10") (pintype "bidirectional"))
    )
    (net (code "68") (name "SDA-1") (class "Default")
      (node (ref "R1-2C") (pin "2") (pinfunction "2_2") (pintype "passive"))
      (node (ref "U0-C") (pin "99") (pinfunction "PC9_99") (pintype "bidirectional"))
      (node (ref "U2-C") (pin "9") (pinfunction "SDA_9") (pintype "bidirectional"))
    )
    (net (code "69") (name "SENSE_A") (class "Default")
      (node (ref "J3-CP") (pin "1") (pinfunction "1_1") (pintype "passive"))
      (node (ref "U0-C") (pin "18") (pinfunction "PF6_18") (pintype "bidirectional"))
      (node (ref "U2-C") (pin "4") (pinfunction "AIN0_4") (pintype "bidirectional"))
    )
    (net (code "70") (name "SENSE_B") (class "Default")
      (node (ref "J3-CP") (pin "2") (pinfunction "2_2") (pintype "passive"))
      (node (ref "U0-C") (pin "19") (pinfunction "PF7_19") (pintype "bidirectional"))
      (node (ref "U2-C") (pin "5") (pinfunction "AIN1_5") (pintype "bidirectional"))
    )
    (net (code "71") (name "SENSE_C") (class "Default")
      (node (ref "J3-CP") (pin "3") (pinfunction "3_3") (pintype "passive"))
      (node (ref "U0-C") (pin "20") (pinfunction "PF8_20") (pintype "bidirectional"))
      (node (ref "U2-C") (pin "6") (pinfunction "AIN2_6") (pintype "bidirectional"))
    )
    (net (code "72") (name "SENSE_D") (class "Default")
      (node (ref "J3-CP") (pin "4") (pinfunction "4_4") (pintype "passive"))
      (node (ref "U0-C") (pin "21") (pinfunction "PF9_21") (pintype "bidirectional"))
      (node (ref "U2-C") (pin "7") (pinfunction "AIN3_7") (pintype "bidirectional"))
    )
    (net (code "73") (name "SENSOR-ERROR") (class "Default")
      (node (ref "J3-CS") (pin "2") (pinfunction "2_2") (pintype "passive"))
      (node (ref "U0-C") (pin "64") (pinfunction "PE11_64") (pintype "bidirectional"))
    )
    (net (code "74") (name "SENSOR-NOMINAL") (class "Default")
      (node (ref "J3-CS") (pin "1") (pinfunction "1_1") (pintype "passive"))
      (node (ref "U0-C") (pin "63") (pinfunction "PE10_63") (pintype "bidirectional"))
    )
    (net (code "75") (name "STORAGE-ERROR") (class "Default")
      (node (ref "R5-C") (pin "1") (pinfunction "1_1") (pintype "passive"))
      (node (ref "U0-C") (pin "58") (pinfunction "PE7_58") (pintype "bidirectional"))
    )
    (net (code "76") (name "SWCLK") (class "Default")
      (node (ref "R4-J1C") (pin "2") (pinfunction "2_2") (pintype "passive"))
      (node (ref "U0-C") (pin "109") (pinfunction "PA14_109") (pintype "bidirectional"))
    )
    (net (code "77") (name "SWDIO") (class "Default")
      (node (ref "R3-J1C") (pin "2") (pinfunction "2_2") (pintype "passive"))
      (node (ref "U0-C") (pin "105") (pinfunction "PA13_105") (pintype "bidirectional"))
    )
    (net (code "78") (name "SWO") (class "Default")
      (node (ref "R1-J1C") (pin "2") (pinfunction "2_2") (pintype "passive"))
      (node (ref "U0-C") (pin "133") (pinfunction "PB3_133") (pintype "bidirectional"))
    )
    (net (code "79") (name "U1S-CHECK") (class "Default")
      (node (ref "J3-CS") (pin "3") (pinfunction "3_3") (pintype "passive"))
      (node (ref "U0-C") (pin "65") (pinfunction "PE12_65") (pintype "bidirectional"))
    )
    (net (code "80") (name "U2S-CHECK") (class "Default")
      (node (ref "J3-CS") (pin "4") (pinfunction "4_4") (pintype "passive"))
      (node (ref "U0-C") (pin "66") (pinfunction "PE13_66") (pintype "bidirectional"))
    )
    (net (code "81") (name "U2S-ST") (class "Default")
      (node (ref "J3-CS") (pin "7") (pinfunction "7_7") (pintype "passive"))
      (node (ref "U0-C") (pin "69") (pinfunction "PB10_69") (pintype "bidirectional"))
    )
    (net (code "82") (name "U3S-CHECK") (class "Default")
      (node (ref "J3-CS") (pin "5") (pinfunction "5_5") (pintype "passive"))
      (node (ref "U0-C") (pin "67") (pinfunction "PE14_67") (pintype "bidirectional"))
    )
    (net (code "83") (name "U4S-CHECK") (class "Default")
      (node (ref "J3-CS") (pin "6") (pinfunction "6_6") (pintype "passive"))
      (node (ref "U0-C") (pin "68") (pinfunction "PE15_68") (pintype "bidirectional"))
    )
    (net (code "84") (name "US2-STATUS") (class "Default")
      (node (ref "J3-CS") (pin "8") (pinfunction "8_8") (pintype "passive"))
      (node (ref "U0-C") (pin "70") (pinfunction "PB11_70") (pintype "bidirectional"))
    )
    (net (code "85") (name "VDDA") (class "Default")
      (node (ref "FB1-0C") (pin "2") (pinfunction "2_2") (pintype "bidirectional"))
      (node (ref "U0-C") (pin "32") (pinfunction "VREF+_32") (pintype "input"))
      (node (ref "U0-C") (pin "33") (pinfunction "VDDA_33") (pintype "power_in"))
    )
    (net (code "86") (name "VUSB") (class "Default")
      (node (ref "J2-C") (pin "1") (pinfunction "VBUS_1") (pintype "power_in"))
      (node (ref "JP-CP") (pin "4") (pinfunction "4_4") (pintype "passive"))
    )
    (net (code "87") (name "WP") (class "Default")
      (node (ref "U0-C") (pin "115") (pinfunction "PD1_115") (pintype "bidirectional"))
      (node (ref "U1-C") (pin "3") (pinfunction "~{WP}/IO2_3") (pintype "bidirectional"))
    )
    (net (code "88") (name "unconnected-(JP-CS-Pad4)") (class "Default")
      (node (ref "JP-CS") (pin "4") (pinfunction "4_4") (pintype "passive"))
    )
    (net (code "89") (name "unconnected-(S0-0C-P1-Pad4)") (class "Default")
      (node (ref "S0-0C") (pin "4") (pinfunction "P1_4") (pintype "passive"))
    )
    (net (code "90") (name "unconnected-(S0-0C-S1-Pad2)") (class "Default")
      (node (ref "S0-0C") (pin "2") (pinfunction "S1_2") (pintype "passive"))
    )
    (net (code "91") (name "unconnected-(U0-C-PA4-Pad40)") (class "Default")
      (node (ref "U0-C") (pin "40") (pinfunction "PA4_40") (pintype "bidirectional"))
    )
    (net (code "92") (name "unconnected-(U0-C-PA9-Pad101)") (class "Default")
      (node (ref "U0-C") (pin "101") (pinfunction "PA9_101") (pintype "bidirectional"))
    )
    (net (code "93") (name "unconnected-(U0-C-PA15-Pad110)") (class "Default")
      (node (ref "U0-C") (pin "110") (pinfunction "PA15_110") (pintype "bidirectional"))
    )
    (net (code "94") (name "unconnected-(U0-C-PB2-Pad48)") (class "Default")
      (node (ref "U0-C") (pin "48") (pinfunction "PB2_48") (pintype "bidirectional"))
    )
    (net (code "95") (name "unconnected-(U0-C-PB4-Pad134)") (class "Default")
      (node (ref "U0-C") (pin "134") (pinfunction "PB4_134") (pintype "bidirectional"))
    )
    (net (code "96") (name "unconnected-(U0-C-PB5-Pad135)") (class "Default")
      (node (ref "U0-C") (pin "135") (pinfunction "PB5_135") (pintype "bidirectional"))
    )
    (net (code "97") (name "unconnected-(U0-C-PB6-Pad136)") (class "Default")
      (node (ref "U0-C") (pin "136") (pinfunction "PB6_136") (pintype "bidirectional"))
    )
    (net (code "98") (name "unconnected-(U0-C-PB7-Pad137)") (class "Default")
      (node (ref "U0-C") (pin "137") (pinfunction "PB7_137") (pintype "bidirectional"))
    )
    (net (code "99") (name "unconnected-(U0-C-PB8-Pad139)") (class "Default")
      (node (ref "U0-C") (pin "139") (pinfunction "PB8_139") (pintype "bidirectional"))
    )
    (net (code "100") (name "unconnected-(U0-C-PB9-Pad140)") (class "Default")
      (node (ref "U0-C") (pin "140") (pinfunction "PB9_140") (pintype "bidirectional"))
    )
    (net (code "101") (name "unconnected-(U0-C-PB12-Pad73)") (class "Default")
      (node (ref "U0-C") (pin "73") (pinfunction "PB12_73") (pintype "bidirectional"))
    )
    (net (code "102") (name "unconnected-(U0-C-PB13-Pad74)") (class "Default")
      (node (ref "U0-C") (pin "74") (pinfunction "PB13_74") (pintype "bidirectional"))
    )
    (net (code "103") (name "unconnected-(U0-C-PB14-Pad75)") (class "Default")
      (node (ref "U0-C") (pin "75") (pinfunction "PB14_75") (pintype "bidirectional"))
    )
    (net (code "104") (name "unconnected-(U0-C-PB15-Pad76)") (class "Default")
      (node (ref "U0-C") (pin "76") (pinfunction "PB15_76") (pintype "bidirectional"))
    )
    (net (code "105") (name "unconnected-(U0-C-PC0-Pad26)") (class "Default")
      (node (ref "U0-C") (pin "26") (pinfunction "PC0_26") (pintype "bidirectional"))
    )
    (net (code "106") (name "unconnected-(U0-C-PC1-Pad27)") (class "Default")
      (node (ref "U0-C") (pin "27") (pinfunction "PC1_27") (pintype "bidirectional"))
    )
    (net (code "107") (name "unconnected-(U0-C-PC2-Pad28)") (class "Default")
      (node (ref "U0-C") (pin "28") (pinfunction "PC2_28") (pintype "bidirectional"))
    )
    (net (code "108") (name "unconnected-(U0-C-PC3-Pad29)") (class "Default")
      (node (ref "U0-C") (pin "29") (pinfunction "PC3_29") (pintype "bidirectional"))
    )
    (net (code "109") (name "unconnected-(U0-C-PC13-Pad7)") (class "Default")
      (node (ref "U0-C") (pin "7") (pinfunction "PC13_7") (pintype "bidirectional"))
    )
    (net (code "110") (name "unconnected-(U0-C-PC14-Pad8)") (class "Default")
      (node (ref "U0-C") (pin "8") (pinfunction "PC14_8") (pintype "bidirectional"))
    )
    (net (code "111") (name "unconnected-(U0-C-PC15-Pad9)") (class "Default")
      (node (ref "U0-C") (pin "9") (pinfunction "PC15_9") (pintype "bidirectional"))
    )
    (net (code "112") (name "unconnected-(U0-C-PD3-Pad117)") (class "Default")
      (node (ref "U0-C") (pin "117") (pinfunction "PD3_117") (pintype "bidirectional"))
    )
    (net (code "113") (name "unconnected-(U0-C-PD4-Pad118)") (class "Default")
      (node (ref "U0-C") (pin "118") (pinfunction "PD4_118") (pintype "bidirectional"))
    )
    (net (code "114") (name "unconnected-(U0-C-PD5-Pad119)") (class "Default")
      (node (ref "U0-C") (pin "119") (pinfunction "PD5_119") (pintype "bidirectional"))
    )
    (net (code "115") (name "unconnected-(U0-C-PD6-Pad122)") (class "Default")
      (node (ref "U0-C") (pin "122") (pinfunction "PD6_122") (pintype "bidirectional"))
    )
    (net (code "116") (name "unconnected-(U0-C-PD7-Pad123)") (class "Default")
      (node (ref "U0-C") (pin "123") (pinfunction "PD7_123") (pintype "bidirectional"))
    )
    (net (code "117") (name "unconnected-(U0-C-PD8-Pad77)") (class "Default")
      (node (ref "U0-C") (pin "77") (pinfunction "PD8_77") (pintype "bidirectional"))
    )
    (net (code "118") (name "unconnected-(U0-C-PD9-Pad78)") (class "Default")
      (node (ref "U0-C") (pin "78") (pinfunction "PD9_78") (pintype "bidirectional"))
    )
    (net (code "119") (name "unconnected-(U0-C-PD10-Pad79)") (class "Default")
      (node (ref "U0-C") (pin "79") (pinfunction "PD10_79") (pintype "bidirectional"))
    )
    (net (code "120") (name "unconnected-(U0-C-PD11-Pad80)") (class "Default")
      (node (ref "U0-C") (pin "80") (pinfunction "PD11_80") (pintype "bidirectional"))
    )
    (net (code "121") (name "unconnected-(U0-C-PD12-Pad81)") (class "Default")
      (node (ref "U0-C") (pin "81") (pinfunction "PD12_81") (pintype "bidirectional"))
    )
    (net (code "122") (name "unconnected-(U0-C-PD13-Pad82)") (class "Default")
      (node (ref "U0-C") (pin "82") (pinfunction "PD13_82") (pintype "bidirectional"))
    )
    (net (code "123") (name "unconnected-(U0-C-PD14-Pad85)") (class "Default")
      (node (ref "U0-C") (pin "85") (pinfunction "PD14_85") (pintype "bidirectional"))
    )
    (net (code "124") (name "unconnected-(U0-C-PD15-Pad86)") (class "Default")
      (node (ref "U0-C") (pin "86") (pinfunction "PD15_86") (pintype "bidirectional"))
    )
    (net (code "125") (name "unconnected-(U0-C-PE0-Pad141)") (class "Default")
      (node (ref "U0-C") (pin "141") (pinfunction "PE0_141") (pintype "bidirectional"))
    )
    (net (code "126") (name "unconnected-(U0-C-PE1-Pad142)") (class "Default")
      (node (ref "U0-C") (pin "142") (pinfunction "PE1_142") (pintype "bidirectional"))
    )
    (net (code "127") (name "unconnected-(U0-C-PE3-Pad2)") (class "Default")
      (node (ref "U0-C") (pin "2") (pinfunction "PE3_2") (pintype "bidirectional"))
    )
    (net (code "128") (name "unconnected-(U0-C-PE4-Pad3)") (class "Default")
      (node (ref "U0-C") (pin "3") (pinfunction "PE4_3") (pintype "bidirectional"))
    )
    (net (code "129") (name "unconnected-(U0-C-PE5-Pad4)") (class "Default")
      (node (ref "U0-C") (pin "4") (pinfunction "PE5_4") (pintype "bidirectional"))
    )
    (net (code "130") (name "unconnected-(U0-C-PE6-Pad5)") (class "Default")
      (node (ref "U0-C") (pin "5") (pinfunction "PE6_5") (pintype "bidirectional"))
    )
    (net (code "131") (name "unconnected-(U0-C-PE9-Pad60)") (class "Default")
      (node (ref "U0-C") (pin "60") (pinfunction "PE9_60") (pintype "bidirectional"))
    )
    (net (code "132") (name "unconnected-(U0-C-PF0-Pad10)") (class "Default")
      (node (ref "U0-C") (pin "10") (pinfunction "PF0_10") (pintype "bidirectional"))
    )
    (net (code "133") (name "unconnected-(U0-C-PF5-Pad15)") (class "Default")
      (node (ref "U0-C") (pin "15") (pinfunction "PF5_15") (pintype "bidirectional"))
    )
    (net (code "134") (name "unconnected-(U0-C-PF10-Pad22)") (class "Default")
      (node (ref "U0-C") (pin "22") (pinfunction "PF10_22") (pintype "bidirectional"))
    )
    (net (code "135") (name "unconnected-(U0-C-PF11-Pad49)") (class "Default")
      (node (ref "U0-C") (pin "49") (pinfunction "PF11_49") (pintype "bidirectional"))
    )
    (net (code "136") (name "unconnected-(U0-C-PF12-Pad50)") (class "Default")
      (node (ref "U0-C") (pin "50") (pinfunction "PF12_50") (pintype "bidirectional"))
    )
    (net (code "137") (name "unconnected-(U0-C-PG2-Pad87)") (class "Default")
      (node (ref "U0-C") (pin "87") (pinfunction "PG2_87") (pintype "bidirectional"))
    )
    (net (code "138") (name "unconnected-(U0-C-PG3-Pad88)") (class "Default")
      (node (ref "U0-C") (pin "88") (pinfunction "PG3_88") (pintype "bidirectional"))
    )
    (net (code "139") (name "unconnected-(U0-C-PG5-Pad90)") (class "Default")
      (node (ref "U0-C") (pin "90") (pinfunction "PG5_90") (pintype "bidirectional"))
    )
    (net (code "140") (name "unconnected-(U0-C-PG6-Pad91)") (class "Default")
      (node (ref "U0-C") (pin "91") (pinfunction "PG6_91") (pintype "bidirectional"))
    )
    (net (code "141") (name "unconnected-(U0-C-PG7-Pad92)") (class "Default")
      (node (ref "U0-C") (pin "92") (pinfunction "PG7_92") (pintype "bidirectional"))
    )
    (net (code "142") (name "unconnected-(U0-C-PG8-Pad93)") (class "Default")
      (node (ref "U0-C") (pin "93") (pinfunction "PG8_93") (pintype "bidirectional"))
    )
    (net (code "143") (name "unconnected-(U0-C-PG9-Pad124)") (class "Default")
      (node (ref "U0-C") (pin "124") (pinfunction "PG9_124") (pintype "bidirectional"))
    )
    (net (code "144") (name "unconnected-(U0-C-PG10-Pad125)") (class "Default")
      (node (ref "U0-C") (pin "125") (pinfunction "PG10_125") (pintype "bidirectional"))
    )
    (net (code "145") (name "unconnected-(U0-C-PG11-Pad126)") (class "Default")
      (node (ref "U0-C") (pin "126") (pinfunction "PG11_126") (pintype "bidirectional"))
    )
    (net (code "146") (name "unconnected-(U0-C-PG12-Pad127)") (class "Default")
      (node (ref "U0-C") (pin "127") (pinfunction "PG12_127") (pintype "bidirectional"))
    )
    (net (code "147") (name "unconnected-(U0-C-PG13-Pad128)") (class "Default")
      (node (ref "U0-C") (pin "128") (pinfunction "PG13_128") (pintype "bidirectional"))
    )
    (net (code "148") (name "unconnected-(U0-C-PG14-Pad129)") (class "Default")
      (node (ref "U0-C") (pin "129") (pinfunction "PG14_129") (pintype "bidirectional"))
    )
    (net (code "149") (name "unconnected-(U0-C-PG15-Pad132)") (class "Default")
      (node (ref "U0-C") (pin "132") (pinfunction "PG15_132") (pintype "bidirectional"))
    )
    (net (code "150") (name "unconnected-(U1-C-EP-Pad9)") (class "Default")
      (node (ref "U1-C") (pin "9") (pinfunction "EP_9") (pintype "bidirectional"))
    )
  )
)
